# DisplayAddOn_V012.net
KiCad netlist of a schematic drawn in EAGLE
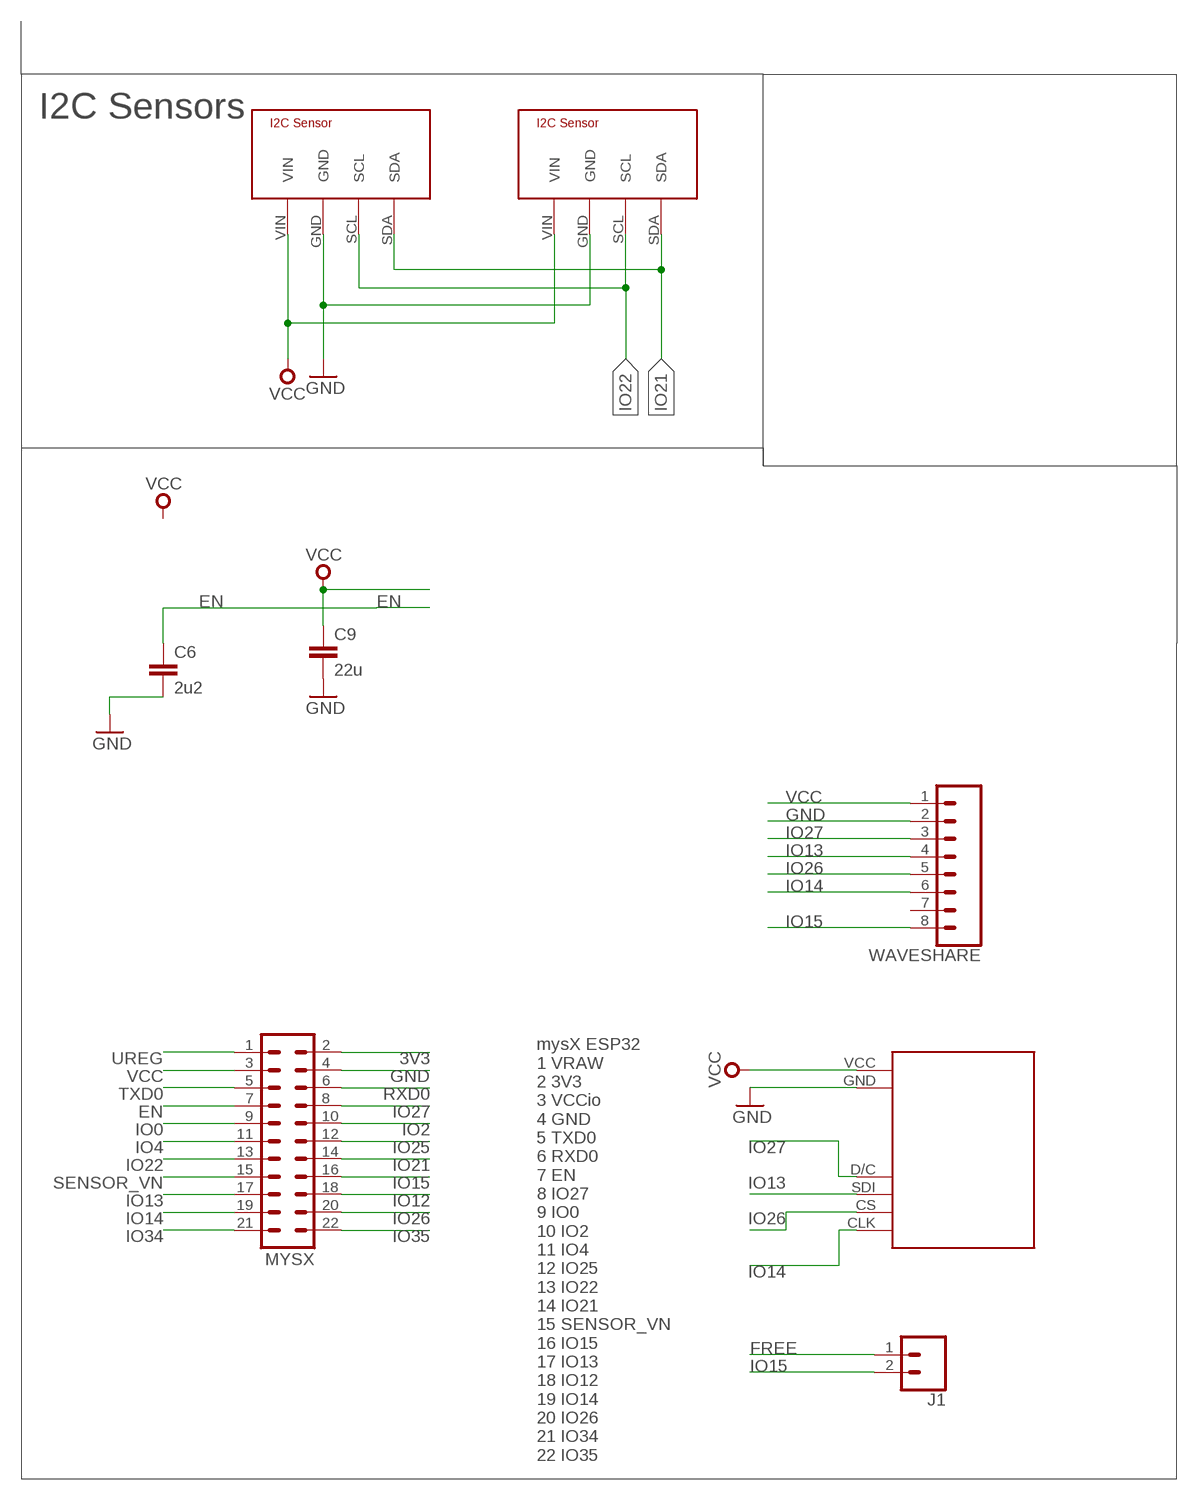
[diagram p0: schematic, sheet 1]

(export (version "E")
  (design (tool "Eeschema 10.0.6"))
  (components
    (comp (ref "C6")
      (value "2u2")
      (footprint "eagle-import:C0805")
      (libsource (lib "eagle-import") (part "C-EUC0805"))
    )
    (comp (ref "C9")
      (value "22u")
      (footprint "eagle-import:C0805")
      (libsource (lib "eagle-import") (part "C-EUC0805"))
    )
    (comp (ref "HELTEK")
      (value "HELTEC_1.54STANDARD1")
      (footprint "eagle-import:HELTEC_1.54INCH")
      (libsource (lib "eagle-import") (part "HELTEC_1.54STANDARD1"))
    )
    (comp (ref "J1")
      (value "CONN_02")
      (footprint "eagle-import:1X02")
      (libsource (lib "eagle-import") (part "CONN_02"))
    )
    (comp (ref "MYSX")
      (value "MA11-2")
      (footprint "eagle-import:MA11-2")
      (libsource (lib "eagle-import") (part "MA11-2"))
    )
    (comp (ref "U$2")
      (value "I2C-BREAKOUT")
      (footprint "eagle-import:I2C_BREAKOUT")
      (libsource (lib "eagle-import") (part "I2C-BREAKOUT"))
    )
    (comp (ref "U$4")
      (value "I2C-BREAKOUT")
      (footprint "eagle-import:I2C_BREAKOUT")
      (libsource (lib "eagle-import") (part "I2C-BREAKOUT"))
    )
    (comp (ref "WAVESHARE")
      (value "CONN_08\"")
      (footprint "eagle-import:1X08")
      (libsource (lib "eagle-import") (part "CONN_08{dblquote}"))
    )
  )
  (nets
    (net (code "1") (name "/3V3") (class "Default")
      (node (ref "MYSX") (pin "2") (pinfunction "2_2") (pintype "passive"))
    )
    (net (code "2") (name "/EN") (class "Default")
      (node (ref "C6") (pin "1") (pinfunction "1_1") (pintype "passive"))
      (node (ref "MYSX") (pin "7") (pinfunction "7_7") (pintype "passive"))
    )
    (net (code "3") (name "/FREE") (class "Default")
      (node (ref "J1") (pin "1") (pinfunction "1_1") (pintype "passive"))
    )
    (net (code "4") (name "/IO0") (class "Default")
      (node (ref "MYSX") (pin "9") (pinfunction "9_9") (pintype "passive"))
    )
    (net (code "5") (name "/IO2") (class "Default")
      (node (ref "MYSX") (pin "10") (pinfunction "10_10") (pintype "passive"))
    )
    (net (code "6") (name "/IO4") (class "Default")
      (node (ref "MYSX") (pin "11") (pinfunction "11_11") (pintype "passive"))
    )
    (net (code "7") (name "/IO12") (class "Default")
      (node (ref "MYSX") (pin "18") (pinfunction "18_18") (pintype "passive"))
    )
    (net (code "8") (name "/IO13") (class "Default")
      (node (ref "HELTEK") (pin "SDI") (pinfunction "SDI_SDI") (pintype "bidirectional"))
      (node (ref "MYSX") (pin "17") (pinfunction "17_17") (pintype "passive"))
      (node (ref "WAVESHARE") (pin "4") (pinfunction "4_4") (pintype "passive"))
    )
    (net (code "9") (name "/IO14") (class "Default")
      (node (ref "HELTEK") (pin "CLK") (pinfunction "CLK_CLK") (pintype "bidirectional"))
      (node (ref "MYSX") (pin "19") (pinfunction "19_19") (pintype "passive"))
      (node (ref "WAVESHARE") (pin "6") (pinfunction "6_6") (pintype "passive"))
    )
    (net (code "10") (name "/IO15") (class "Default")
      (node (ref "J1") (pin "2") (pinfunction "2_2") (pintype "passive"))
      (node (ref "MYSX") (pin "16") (pinfunction "16_16") (pintype "passive"))
      (node (ref "WAVESHARE") (pin "8") (pinfunction "8_8") (pintype "passive"))
    )
    (net (code "11") (name "/IO25") (class "Default")
      (node (ref "MYSX") (pin "12") (pinfunction "12_12") (pintype "passive"))
    )
    (net (code "12") (name "/IO26") (class "Default")
      (node (ref "HELTEK") (pin "CS") (pinfunction "CS_CS") (pintype "bidirectional"))
      (node (ref "MYSX") (pin "20") (pinfunction "20_20") (pintype "passive"))
      (node (ref "WAVESHARE") (pin "5") (pinfunction "5_5") (pintype "passive"))
    )
    (net (code "13") (name "/IO27") (class "Default")
      (node (ref "HELTEK") (pin "D/C") (pinfunction "D/C_D/C") (pintype "bidirectional"))
      (node (ref "MYSX") (pin "8") (pinfunction "8_8") (pintype "passive"))
      (node (ref "WAVESHARE") (pin "3") (pinfunction "3_3") (pintype "passive"))
    )
    (net (code "14") (name "/IO34") (class "Default")
      (node (ref "MYSX") (pin "21") (pinfunction "21_21") (pintype "passive"))
    )
    (net (code "15") (name "/IO35") (class "Default")
      (node (ref "MYSX") (pin "22") (pinfunction "22_22") (pintype "passive"))
    )
    (net (code "16") (name "/RXD0") (class "Default")
      (node (ref "MYSX") (pin "6") (pinfunction "6_6") (pintype "passive"))
    )
    (net (code "17") (name "/SENSOR_VN") (class "Default")
      (node (ref "MYSX") (pin "15") (pinfunction "15_15") (pintype "passive"))
    )
    (net (code "18") (name "/TXD0") (class "Default")
      (node (ref "MYSX") (pin "5") (pinfunction "5_5") (pintype "passive"))
    )
    (net (code "19") (name "/UREG") (class "Default")
      (node (ref "MYSX") (pin "1") (pinfunction "1_1") (pintype "passive"))
    )
    (net (code "20") (name "GND") (class "Default")
      (node (ref "C6") (pin "2") (pinfunction "2_2") (pintype "passive"))
      (node (ref "C9") (pin "2") (pinfunction "2_2") (pintype "passive"))
      (node (ref "HELTEK") (pin "GND") (pinfunction "GND_GND") (pintype "power_in"))
      (node (ref "MYSX") (pin "4") (pinfunction "4_4") (pintype "passive"))
      (node (ref "U$2") (pin "GND") (pinfunction "GND_GND") (pintype "bidirectional"))
      (node (ref "U$4") (pin "GND") (pinfunction "GND_GND") (pintype "bidirectional"))
      (node (ref "WAVESHARE") (pin "2") (pinfunction "2_2") (pintype "passive"))
    )
    (net (code "21") (name "IO21") (class "Default")
      (node (ref "MYSX") (pin "14") (pinfunction "14_14") (pintype "passive"))
      (node (ref "U$2") (pin "SDA") (pinfunction "SDA_SDA") (pintype "bidirectional"))
      (node (ref "U$4") (pin "SDA") (pinfunction "SDA_SDA") (pintype "bidirectional"))
    )
    (net (code "22") (name "IO22") (class "Default")
      (node (ref "MYSX") (pin "13") (pinfunction "13_13") (pintype "passive"))
      (node (ref "U$2") (pin "SCL") (pinfunction "SCL_SCL") (pintype "bidirectional"))
      (node (ref "U$4") (pin "SCL") (pinfunction "SCL_SCL") (pintype "bidirectional"))
    )
    (net (code "23") (name "VCC") (class "Default")
      (node (ref "C9") (pin "1") (pinfunction "1_1") (pintype "passive"))
      (node (ref "HELTEK") (pin "VCC") (pinfunction "VCC_VCC") (pintype "power_in"))
      (node (ref "MYSX") (pin "3") (pinfunction "3_3") (pintype "passive"))
      (node (ref "U$2") (pin "VIN") (pinfunction "VIN_VIN") (pintype "bidirectional"))
      (node (ref "U$4") (pin "VIN") (pinfunction "VIN_VIN") (pintype "bidirectional"))
      (node (ref "WAVESHARE") (pin "1") (pinfunction "1_1") (pintype "passive"))
    )
    (net (code "24") (name "unconnected-(WAVESHARE-Pad7)") (class "Default")
      (node (ref "WAVESHARE") (pin "7") (pinfunction "7_7") (pintype "passive"))
    )
  )
)
